# TAH_Remote_Shield.net
KiCad netlist of a schematic drawn in EAGLE
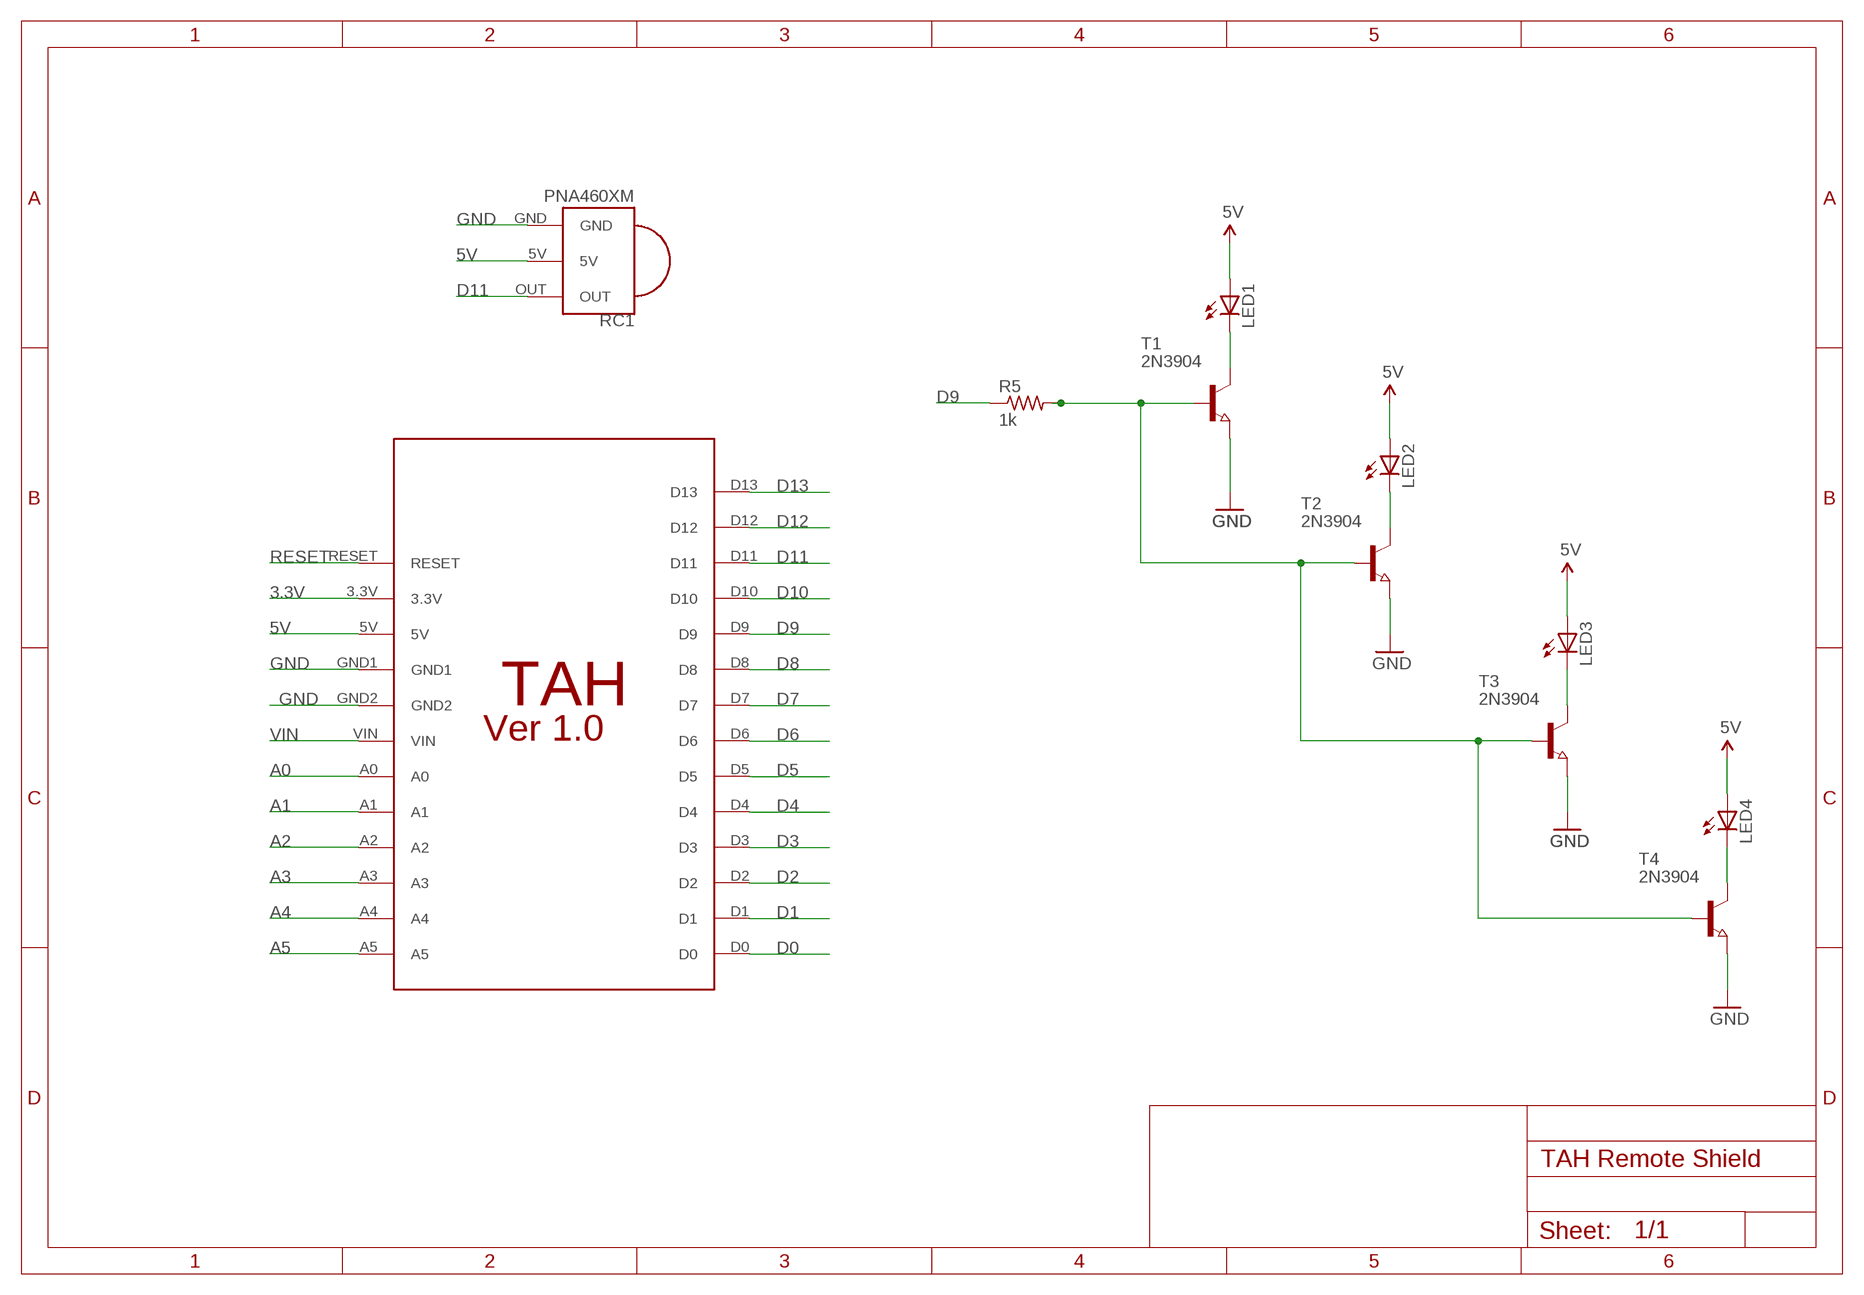
[diagram p0: schematic, sheet 1]

(export (version "E")
  (design (tool "Eeschema 10.0.6"))
  (components
    (comp (ref "LED1")
      (value "LED5MM")
      (footprint "eagle-import:LED5MM")
      (libsource (lib "eagle-import") (part "LED5MM"))
    )
    (comp (ref "LED2")
      (value "LED5MM")
      (footprint "eagle-import:LED5MM")
      (libsource (lib "eagle-import") (part "LED5MM"))
    )
    (comp (ref "LED3")
      (value "LED5MM")
      (footprint "eagle-import:LED5MM")
      (libsource (lib "eagle-import") (part "LED5MM"))
    )
    (comp (ref "LED4")
      (value "LED5MM")
      (footprint "eagle-import:LED5MM")
      (libsource (lib "eagle-import") (part "LED5MM"))
    )
    (comp (ref "R5")
      (value "1k")
      (footprint "eagle-import:M1206")
      (libsource (lib "eagle-import") (part "R-US_M1206"))
    )
    (comp (ref "RC1")
      (value "PNA460XM")
      (footprint "eagle-import:PNA460XM")
      (libsource (lib "eagle-import") (part "PNA460XM"))
    )
    (comp (ref "T1")
      (value "2N3904")
      (footprint "eagle-import:SOT23")
      (libsource (lib "eagle-import") (part "NPN-TRANSISTOR_SOT23"))
    )
    (comp (ref "T2")
      (value "2N3904")
      (footprint "eagle-import:SOT23")
      (libsource (lib "eagle-import") (part "NPN-TRANSISTOR_SOT23"))
    )
    (comp (ref "T3")
      (value "2N3904")
      (footprint "eagle-import:SOT23")
      (libsource (lib "eagle-import") (part "NPN-TRANSISTOR_SOT23"))
    )
    (comp (ref "T4")
      (value "2N3904")
      (footprint "eagle-import:SOT23")
      (libsource (lib "eagle-import") (part "NPN-TRANSISTOR_SOT23"))
    )
    (comp (ref "U$2")
      (value "TAH_PIN_FOOTPRINT_WITHOUT_ICSP_VER1.0")
      (footprint "eagle-import:TAH_PIN_FOOTPRINT_WITHOUT_ICSP_VER1.0")
      (libsource (lib "eagle-import") (part "TAH_PIN_FOOTPRINT_WITHOUT_ICSP_VER1.0"))
    )
  )
  (nets
    (net (code "1") (name "/3.3V") (class "Default")
      (node (ref "U$2") (pin "3.3V") (pinfunction "3.3V_3.3V") (pintype "bidirectional"))
    )
    (net (code "2") (name "/A0") (class "Default")
      (node (ref "U$2") (pin "A0") (pinfunction "A0_A0") (pintype "bidirectional"))
    )
    (net (code "3") (name "/A1") (class "Default")
      (node (ref "U$2") (pin "A1") (pinfunction "A1_A1") (pintype "bidirectional"))
    )
    (net (code "4") (name "/A2") (class "Default")
      (node (ref "U$2") (pin "A2") (pinfunction "A2_A2") (pintype "bidirectional"))
    )
    (net (code "5") (name "/A3") (class "Default")
      (node (ref "U$2") (pin "A3") (pinfunction "A3_A3") (pintype "bidirectional"))
    )
    (net (code "6") (name "/A4") (class "Default")
      (node (ref "U$2") (pin "A4") (pinfunction "A4_A4") (pintype "bidirectional"))
    )
    (net (code "7") (name "/A5") (class "Default")
      (node (ref "U$2") (pin "A5") (pinfunction "A5_A5") (pintype "bidirectional"))
    )
    (net (code "8") (name "/D0") (class "Default")
      (node (ref "U$2") (pin "D0") (pinfunction "D0_D0") (pintype "bidirectional"))
    )
    (net (code "9") (name "/D1") (class "Default")
      (node (ref "U$2") (pin "D1") (pinfunction "D1_D1") (pintype "bidirectional"))
    )
    (net (code "10") (name "/D2") (class "Default")
      (node (ref "U$2") (pin "D2") (pinfunction "D2_D2") (pintype "bidirectional"))
    )
    (net (code "11") (name "/D3") (class "Default")
      (node (ref "U$2") (pin "D3") (pinfunction "D3_D3") (pintype "bidirectional"))
    )
    (net (code "12") (name "/D4") (class "Default")
      (node (ref "U$2") (pin "D4") (pinfunction "D4_D4") (pintype "bidirectional"))
    )
    (net (code "13") (name "/D5") (class "Default")
      (node (ref "U$2") (pin "D5") (pinfunction "D5_D5") (pintype "bidirectional"))
    )
    (net (code "14") (name "/D6") (class "Default")
      (node (ref "U$2") (pin "D6") (pinfunction "D6_D6") (pintype "bidirectional"))
    )
    (net (code "15") (name "/D7") (class "Default")
      (node (ref "U$2") (pin "D7") (pinfunction "D7_D7") (pintype "bidirectional"))
    )
    (net (code "16") (name "/D8") (class "Default")
      (node (ref "U$2") (pin "D8") (pinfunction "D8_D8") (pintype "bidirectional"))
    )
    (net (code "17") (name "/D9") (class "Default")
      (node (ref "R5") (pin "1") (pinfunction "1_1") (pintype "passive"))
      (node (ref "U$2") (pin "D9") (pinfunction "D9_D9") (pintype "bidirectional"))
    )
    (net (code "18") (name "/D10") (class "Default")
      (node (ref "U$2") (pin "D10") (pinfunction "D10_D10") (pintype "bidirectional"))
    )
    (net (code "19") (name "/D11") (class "Default")
      (node (ref "RC1") (pin "OUT") (pinfunction "OUT_OUT") (pintype "output"))
      (node (ref "U$2") (pin "D11") (pinfunction "D11_D11") (pintype "bidirectional"))
    )
    (net (code "20") (name "/D12") (class "Default")
      (node (ref "U$2") (pin "D12") (pinfunction "D12_D12") (pintype "bidirectional"))
    )
    (net (code "21") (name "/D13") (class "Default")
      (node (ref "U$2") (pin "D13") (pinfunction "D13_D13") (pintype "bidirectional"))
    )
    (net (code "22") (name "/RESET") (class "Default")
      (node (ref "U$2") (pin "RESET") (pinfunction "RESET_RESET") (pintype "bidirectional"))
    )
    (net (code "23") (name "/VIN") (class "Default")
      (node (ref "U$2") (pin "VIN") (pinfunction "VIN_VIN") (pintype "bidirectional"))
    )
    (net (code "24") (name "5V") (class "Default")
      (node (ref "LED1") (pin "A") (pinfunction "A_A") (pintype "passive"))
      (node (ref "LED2") (pin "A") (pinfunction "A_A") (pintype "passive"))
      (node (ref "LED3") (pin "A") (pinfunction "A_A") (pintype "passive"))
      (node (ref "LED4") (pin "A") (pinfunction "A_A") (pintype "passive"))
      (node (ref "RC1") (pin "5V") (pinfunction "5V_5V") (pintype "power_in"))
      (node (ref "U$2") (pin "5V") (pinfunction "5V_5V") (pintype "bidirectional"))
    )
    (net (code "25") (name "GND") (class "Default")
      (node (ref "RC1") (pin "GND") (pinfunction "GND_GND") (pintype "power_in"))
      (node (ref "T1") (pin "2") (pinfunction "E_2") (pintype "passive"))
      (node (ref "T2") (pin "2") (pinfunction "E_2") (pintype "passive"))
      (node (ref "T3") (pin "2") (pinfunction "E_2") (pintype "passive"))
      (node (ref "T4") (pin "2") (pinfunction "E_2") (pintype "passive"))
      (node (ref "U$2") (pin "GND1") (pinfunction "GND1_GND1") (pintype "bidirectional"))
      (node (ref "U$2") (pin "GND2") (pinfunction "GND2_GND2") (pintype "bidirectional"))
    )
    (net (code "26") (name "Net-(LED1-C)") (class "Default")
      (node (ref "LED1") (pin "K") (pinfunction "C_K") (pintype "passive"))
      (node (ref "T1") (pin "3") (pinfunction "C_3") (pintype "passive"))
    )
    (net (code "27") (name "Net-(LED2-C)") (class "Default")
      (node (ref "LED2") (pin "K") (pinfunction "C_K") (pintype "passive"))
      (node (ref "T2") (pin "3") (pinfunction "C_3") (pintype "passive"))
    )
    (net (code "28") (name "Net-(LED3-C)") (class "Default")
      (node (ref "LED3") (pin "K") (pinfunction "C_K") (pintype "passive"))
      (node (ref "T3") (pin "3") (pinfunction "C_3") (pintype "passive"))
    )
    (net (code "29") (name "Net-(LED4-C)") (class "Default")
      (node (ref "LED4") (pin "K") (pinfunction "C_K") (pintype "passive"))
      (node (ref "T4") (pin "3") (pinfunction "C_3") (pintype "passive"))
    )
    (net (code "30") (name "Net-(T1-B)") (class "Default")
      (node (ref "R5") (pin "2") (pinfunction "2_2") (pintype "passive"))
      (node (ref "T1") (pin "1") (pinfunction "B_1") (pintype "passive"))
      (node (ref "T2") (pin "1") (pinfunction "B_1") (pintype "passive"))
      (node (ref "T3") (pin "1") (pinfunction "B_1") (pintype "passive"))
      (node (ref "T4") (pin "1") (pinfunction "B_1") (pintype "passive"))
    )
  )
)
